# DB10011_CANTranceiver.net
KiCad netlist of a schematic drawn in Altium Designer
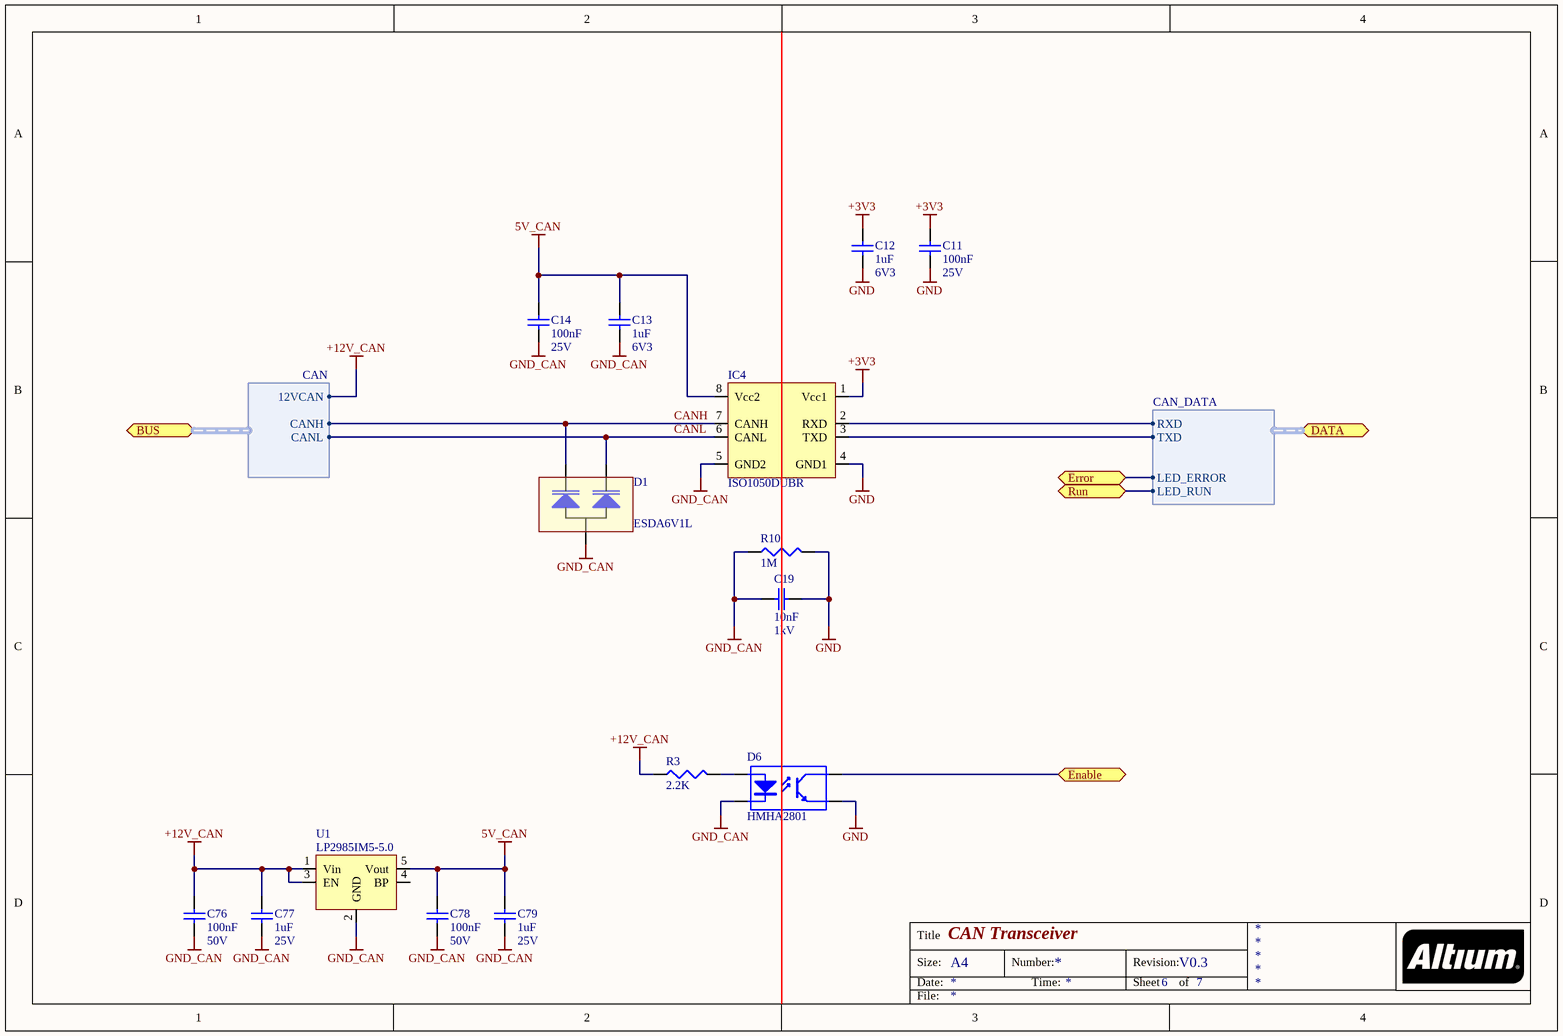
[diagram p0: DB10011_CANTranceiver.SchDoc]

(export (version "E")
  (design (tool "Eeschema 10.0.6"))
  (components
    (comp (ref "C11")
      (value "100nF")
      (footprint "C0402")
      (description "Capacitor, 100nF, 25V, X7R")
      (fields (field (name "VOLTAGE RATING") "25V"))
      (libsource (lib "AR_Capacitors_Ceramic") (part "100nF/0402/CER/25V"))
    )
    (comp (ref "C12")
      (value "1uF")
      (footprint "C0402")
      (description "Capacitor, 1uF, 6.3V, X5R")
      (fields (field (name "VOLTAGE RATING") "6V3"))
      (libsource (lib "AR_Capacitors_Ceramic") (part "1uF/0402/CER/6.3V"))
    )
    (comp (ref "C13")
      (value "1uF")
      (footprint "C0402")
      (description "Capacitor, 1uF, 6.3V, X5R")
      (fields (field (name "VOLTAGE RATING") "6V3"))
      (libsource (lib "AR_Capacitors_Ceramic") (part "1uF/0402/CER/6.3V"))
    )
    (comp (ref "C14")
      (value "100nF")
      (footprint "C0402")
      (description "Capacitor, 100nF, 25V, X7R")
      (fields (field (name "VOLTAGE RATING") "25V"))
      (libsource (lib "AR_Capacitors_Ceramic") (part "100nF/0402/CER/25V"))
    )
    (comp (ref "C19")
      (value "10nF")
      (footprint "C-1206")
      (description "Capacitor, F, 1kV, X7R")
      (fields (field (name "VOLTAGE RATING") "1kV"))
      (libsource (lib "AR_Capacitors_Ceramic") (part "10nF/1206/CER/1kV"))
    )
    (comp (ref "C76")
      (value "100nF")
      (footprint "C0603")
      (description "Capacitor, 100nF, 50V, X7R")
      (fields (field (name "VOLTAGE RATING") "50V"))
      (libsource (lib "AR_Capacitors_Ceramic") (part "100nF/0603/CER/50V"))
    )
    (comp (ref "C77")
      (value "1uF")
      (footprint "C0603")
      (description "Capacitor, 1uF, 25V, X7R")
      (fields (field (name "VOLTAGE RATING") "25V"))
      (libsource (lib "AR_Capacitors_Ceramic") (part "1uF/0603/CER/25V"))
    )
    (comp (ref "C78")
      (value "100nF")
      (footprint "C0603")
      (description "Capacitor, 100nF, 50V, X7R")
      (fields (field (name "VOLTAGE RATING") "50V"))
      (libsource (lib "AR_Capacitors_Ceramic") (part "100nF/0603/CER/50V"))
    )
    (comp (ref "C79")
      (value "1uF")
      (footprint "C0603")
      (description "Capacitor, 1uF, 25V, X7R")
      (fields (field (name "VOLTAGE RATING") "25V"))
      (libsource (lib "AR_Capacitors_Ceramic") (part "1uF/0603/CER/25V"))
    )
    (comp (ref "D1")
      (value "ESDA6V1L")
      (footprint "SOT23")
      (description "Diode TVS Dual, Vrwm: 5.25V, Vbr: 7.2V, Vc: 12.45V, Ippm: 15A")
      (libsource (lib "AR_Diodes") (part "ESDA6V1L"))
    )
    (comp (ref "D6")
      (value "HMHA2801")
      (footprint "FSOP4")
      (description "Optocoupler, Vout:80V, Iin:0.01A")
      (libsource (lib "AR_Optocouplers") (part "HMHA2801"))
    )
    (comp (ref "IC4")
      (value "ISO1050DUBR")
      (footprint "PDSO8")
      (description "CAN TRANSCEIVER")
      (libsource (lib "AR_ICs") (part "ISO1050DUBR"))
    )
    (comp (ref "R3")
      (value "2.2K")
      (footprint "0603")
      (description "Resistor, 2.2K, 1%, 0.063W, 50V, 100PPM, 0603")
      (libsource (lib "AR_Resistors_SMD") (part "2.2K/0603/0063W/50V"))
    )
    (comp (ref "R10")
      (value "1M")
      (footprint "1206")
      (description "Resistor, 1M, 1%, 0.25W, 1kV, 200PPM, 1206")
      (libsource (lib "AR_Resistors_SMD") (part "1M/1206/0300W/1kV"))
    )
    (comp (ref "U1")
      (value "LP2985IM5-5.0")
      (footprint "SOT-23-5")
      (description "LDO, 280mVDO, 5V, 0.15A, 1%")
      (libsource (lib "AR_Vreg") (part "LP2985IM5-5.0"))
    )
  )
  (nets
    (net (code "3") (name "+3V3") (class "Default")
      (node (ref "C11") (pin "2") (pinfunction "2_2") (pintype "passive"))
      (node (ref "C12") (pin "2") (pinfunction "2_2") (pintype "passive"))
      (node (ref "IC4") (pin "1") (pinfunction "Vcc1_1") (pintype "passive"))
    )
    (net (code "4") (name "+12V_CAN") (class "Default")
      (node (ref "C76") (pin "2") (pinfunction "2_2") (pintype "passive"))
      (node (ref "C77") (pin "2") (pinfunction "2_2") (pintype "passive"))
      (node (ref "R3") (pin "2") (pinfunction "2_2") (pintype "passive"))
      (node (ref "U1") (pin "1") (pinfunction "Vin_1") (pintype "passive"))
      (node (ref "U1") (pin "3") (pinfunction "EN_3") (pintype "passive"))
    )
    (net (code "5") (name "/CANH") (class "Default")
      (node (ref "D1") (pin "K1") (pinfunction "K1_K1") (pintype "passive"))
      (node (ref "IC4") (pin "7") (pinfunction "CANH_7") (pintype "passive"))
    )
    (net (code "6") (name "/CANL") (class "Default")
      (node (ref "D1") (pin "K2") (pinfunction "K2_K2") (pintype "passive"))
      (node (ref "IC4") (pin "6") (pinfunction "CANL_6") (pintype "passive"))
    )
    (net (code "7") (name "/Enable") (class "Default")
      (node (ref "D6") (pin "4") (pinfunction "C1_4") (pintype "passive"))
    )
    (net (code "9") (name "/RXD") (class "Default")
      (node (ref "IC4") (pin "2") (pinfunction "RXD_2") (pintype "passive"))
    )
    (net (code "11") (name "/TXD") (class "Default")
      (node (ref "IC4") (pin "3") (pinfunction "TXD_3") (pintype "passive"))
    )
    (net (code "14") (name "5V_CAN") (class "Default")
      (node (ref "C13") (pin "2") (pinfunction "2_2") (pintype "passive"))
      (node (ref "C14") (pin "2") (pinfunction "2_2") (pintype "passive"))
      (node (ref "C78") (pin "2") (pinfunction "2_2") (pintype "passive"))
      (node (ref "C79") (pin "2") (pinfunction "2_2") (pintype "passive"))
      (node (ref "IC4") (pin "8") (pinfunction "Vcc2_8") (pintype "passive"))
      (node (ref "U1") (pin "5") (pinfunction "Vout_5") (pintype "passive"))
    )
    (net (code "15") (name "GND") (class "Default")
      (node (ref "C11") (pin "1") (pinfunction "1_1") (pintype "passive"))
      (node (ref "C12") (pin "1") (pinfunction "1_1") (pintype "passive"))
      (node (ref "C19") (pin "1") (pinfunction "1_1") (pintype "passive"))
      (node (ref "D6") (pin "3") (pinfunction "E1_3") (pintype "passive"))
      (node (ref "IC4") (pin "4") (pinfunction "GND1_4") (pintype "passive"))
      (node (ref "R10") (pin "1") (pinfunction "1_1") (pintype "passive"))
    )
    (net (code "16") (name "GND_CAN") (class "Default")
      (node (ref "C13") (pin "1") (pinfunction "1_1") (pintype "passive"))
      (node (ref "C14") (pin "1") (pinfunction "1_1") (pintype "passive"))
      (node (ref "C19") (pin "2") (pinfunction "2_2") (pintype "passive"))
      (node (ref "C76") (pin "1") (pinfunction "1_1") (pintype "passive"))
      (node (ref "C77") (pin "1") (pinfunction "1_1") (pintype "passive"))
      (node (ref "C78") (pin "1") (pinfunction "1_1") (pintype "passive"))
      (node (ref "C79") (pin "1") (pinfunction "1_1") (pintype "passive"))
      (node (ref "D1") (pin "A") (pinfunction "A_A") (pintype "passive"))
      (node (ref "D6") (pin "2") (pinfunction "K1_2") (pintype "passive"))
      (node (ref "IC4") (pin "5") (pinfunction "GND2_5") (pintype "passive"))
      (node (ref "R10") (pin "2") (pinfunction "2_2") (pintype "passive"))
      (node (ref "U1") (pin "2") (pinfunction "GND_2") (pintype "passive"))
    )
    (net (code "17") (name "Net-(D6-A1)") (class "Default")
      (node (ref "D6") (pin "1") (pinfunction "A1_1") (pintype "passive"))
      (node (ref "R3") (pin "1") (pinfunction "1_1") (pintype "passive"))
    )
    (net (code "18") (name "unconnected-(U1-BP-Pad4)") (class "Default")
      (node (ref "U1") (pin "4") (pinfunction "BP_4") (pintype "passive"))
    )
  )
)
